# RFBoardLayoutGen0_v03_1routingTADworking.net
KiCad netlist of a schematic drawn in EAGLE
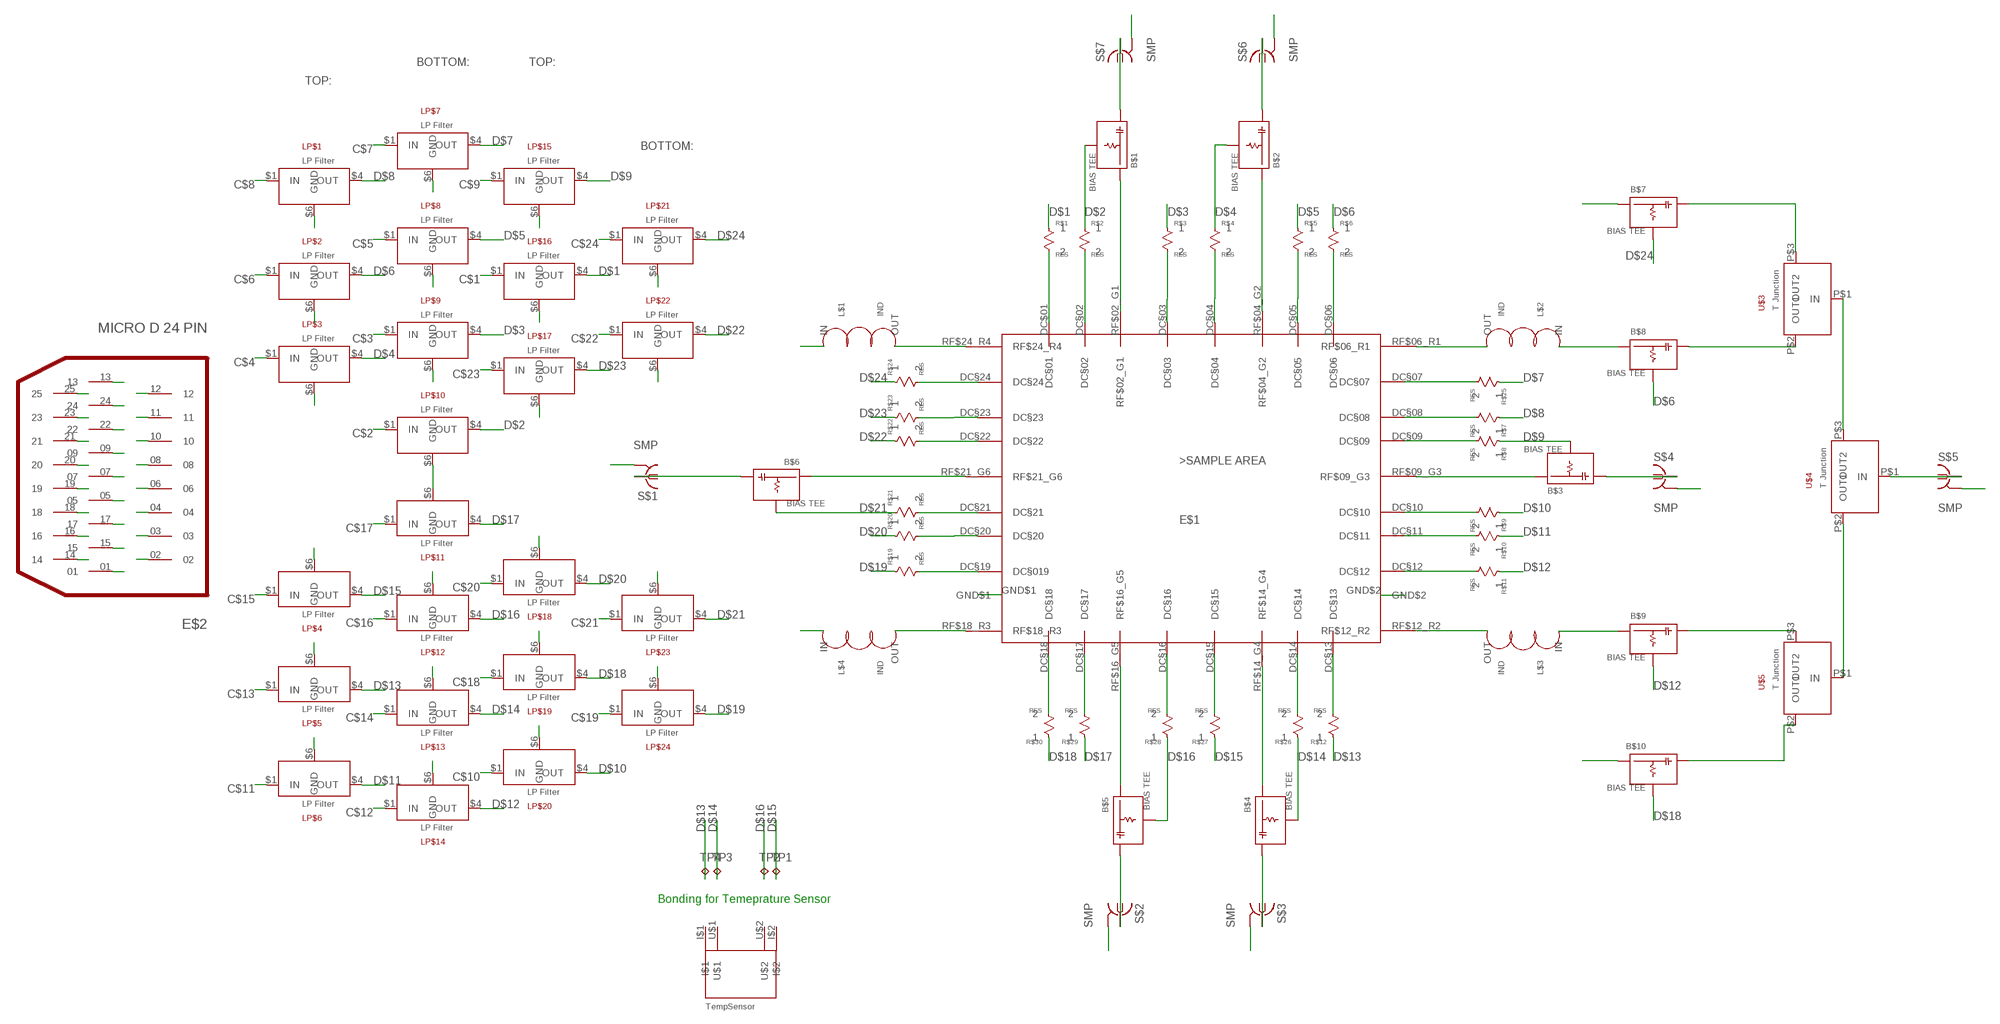
[diagram p0: schematic, sheet 1, part 1 of 2]
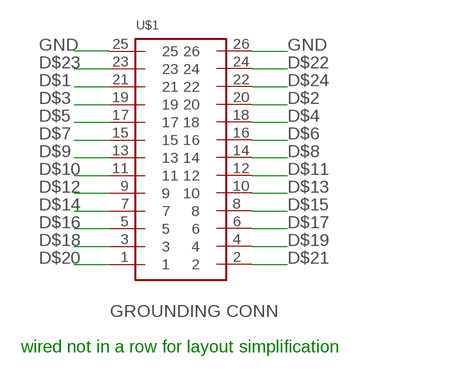
[diagram p1: schematic, sheet 1, part 2 of 2]

(export (version "E")
  (design (tool "Eeschema 10.0.6"))
  (components
    (comp (ref "B$1")
      (value "BIASTEEDOWN")
      (footprint "eagle-import:BIAS_TEE_DOWN_0603")
      (libsource (lib "eagle-import") (part "BIASTEEDOWN"))
    )
    (comp (ref "B$2")
      (value "BIASTEEUP")
      (footprint "eagle-import:BIAS_TEE_UP_0603")
      (libsource (lib "eagle-import") (part "BIASTEEUP"))
    )
    (comp (ref "B$3")
      (value "BIASTEEDOWN")
      (footprint "eagle-import:BIAS_TEE_DOWN_0603")
      (libsource (lib "eagle-import") (part "BIASTEEDOWN"))
    )
    (comp (ref "B$4")
      (value "BIASTEEDOWN")
      (footprint "eagle-import:BIAS_TEE_DOWN_0603")
      (libsource (lib "eagle-import") (part "BIASTEEDOWN"))
    )
    (comp (ref "B$5")
      (value "BIASTEEUP")
      (footprint "eagle-import:BIAS_TEE_UP_0603")
      (libsource (lib "eagle-import") (part "BIASTEEUP"))
    )
    (comp (ref "B$6")
      (value "BIASTEEDOWN")
      (footprint "eagle-import:BIAS_TEE_DOWN_0603")
      (libsource (lib "eagle-import") (part "BIASTEEDOWN"))
    )
    (comp (ref "B$7")
      (value "BIASTEEUP")
      (footprint "eagle-import:BIAS_TEE_UP_0603")
      (libsource (lib "eagle-import") (part "BIASTEEUP"))
    )
    (comp (ref "B$8")
      (value "BIASTEEDOWN")
      (footprint "eagle-import:BIAS_TEE_DOWN_0603")
      (libsource (lib "eagle-import") (part "BIASTEEDOWN"))
    )
    (comp (ref "B$9")
      (value "BIASTEEUP")
      (footprint "eagle-import:BIAS_TEE_UP_0603")
      (libsource (lib "eagle-import") (part "BIASTEEUP"))
    )
    (comp (ref "B$10")
      (value "BIASTEEDOWN")
      (footprint "eagle-import:BIAS_TEE_DOWN_0603")
      (libsource (lib "eagle-import") (part "BIASTEEDOWN"))
    )
    (comp (ref "E$1")
      (value "24DC+10RF")
      (footprint "eagle-import:24DC+10RF_400MU-PADS_0.7X0.7_V1.0")
      (libsource (lib "eagle-import") (part "24DC+10RF"))
    )
    (comp (ref "E$2")
      (value "25_SOCKET_M83513(13-DPINOUT2")
      (footprint "eagle-import:25_SOCKET_M83513_13-D_V2")
      (libsource (lib "eagle-import") (part "25_SOCKET_M83513(13-DPINOUT2"))
    )
    (comp (ref "L$1")
      (value "L_MATCH")
      (footprint "eagle-import:L_MATCH")
      (libsource (lib "eagle-import") (part "L_MATCH"))
    )
    (comp (ref "L$2")
      (value "L_MATCH")
      (footprint "eagle-import:L_MATCH")
      (libsource (lib "eagle-import") (part "L_MATCH"))
    )
    (comp (ref "L$3")
      (value "L_MATCH")
      (footprint "eagle-import:L_MATCH")
      (libsource (lib "eagle-import") (part "L_MATCH"))
    )
    (comp (ref "L$4")
      (value "L_MATCH")
      (footprint "eagle-import:L_MATCH")
      (libsource (lib "eagle-import") (part "L_MATCH"))
    )
    (comp (ref "LP$1")
      (value "LP-FILTER/1-STAGETOP")
      (footprint "eagle-import:LP-FILTER_1_STAGE_OS_0603_TOP")
      (libsource (lib "eagle-import") (part "LP-FILTER/1-STAGETOP"))
    )
    (comp (ref "LP$2")
      (value "LP-FILTER/1-STAGETOP")
      (footprint "eagle-import:LP-FILTER_1_STAGE_OS_0603_TOP")
      (libsource (lib "eagle-import") (part "LP-FILTER/1-STAGETOP"))
    )
    (comp (ref "LP$3")
      (value "LP-FILTER/1-STAGETOP")
      (footprint "eagle-import:LP-FILTER_1_STAGE_OS_0603_TOP")
      (libsource (lib "eagle-import") (part "LP-FILTER/1-STAGETOP"))
    )
    (comp (ref "LP$4")
      (value "LP-FILTER/1-STAGETOP")
      (footprint "eagle-import:LP-FILTER_1_STAGE_OS_0603_TOP")
      (libsource (lib "eagle-import") (part "LP-FILTER/1-STAGETOP"))
    )
    (comp (ref "LP$5")
      (value "LP-FILTER/1-STAGETOP")
      (footprint "eagle-import:LP-FILTER_1_STAGE_OS_0603_TOP")
      (libsource (lib "eagle-import") (part "LP-FILTER/1-STAGETOP"))
    )
    (comp (ref "LP$6")
      (value "LP-FILTER/1-STAGETOP")
      (footprint "eagle-import:LP-FILTER_1_STAGE_OS_0603_TOP")
      (libsource (lib "eagle-import") (part "LP-FILTER/1-STAGETOP"))
    )
    (comp (ref "LP$7")
      (value "LP-FILTER/1-STAGEBOT")
      (footprint "eagle-import:LP-FILTER_1_STAGE_OS_0603_BOTTOM")
      (libsource (lib "eagle-import") (part "LP-FILTER/1-STAGEBOT"))
    )
    (comp (ref "LP$8")
      (value "LP-FILTER/1-STAGEBOT")
      (footprint "eagle-import:LP-FILTER_1_STAGE_OS_0603_BOTTOM")
      (libsource (lib "eagle-import") (part "LP-FILTER/1-STAGEBOT"))
    )
    (comp (ref "LP$9")
      (value "LP-FILTER/1-STAGEBOT")
      (footprint "eagle-import:LP-FILTER_1_STAGE_OS_0603_BOTTOM")
      (libsource (lib "eagle-import") (part "LP-FILTER/1-STAGEBOT"))
    )
    (comp (ref "LP$10")
      (value "LP-FILTER/1-STAGEBOT")
      (footprint "eagle-import:LP-FILTER_1_STAGE_OS_0603_BOTTOM")
      (libsource (lib "eagle-import") (part "LP-FILTER/1-STAGEBOT"))
    )
    (comp (ref "LP$11")
      (value "LP-FILTER/1-STAGEBOT")
      (footprint "eagle-import:LP-FILTER_1_STAGE_OS_0603_BOTTOM")
      (libsource (lib "eagle-import") (part "LP-FILTER/1-STAGEBOT"))
    )
    (comp (ref "LP$12")
      (value "LP-FILTER/1-STAGEBOT")
      (footprint "eagle-import:LP-FILTER_1_STAGE_OS_0603_BOTTOM")
      (libsource (lib "eagle-import") (part "LP-FILTER/1-STAGEBOT"))
    )
    (comp (ref "LP$13")
      (value "LP-FILTER/1-STAGEBOT")
      (footprint "eagle-import:LP-FILTER_1_STAGE_OS_0603_BOTTOM")
      (libsource (lib "eagle-import") (part "LP-FILTER/1-STAGEBOT"))
    )
    (comp (ref "LP$14")
      (value "LP-FILTER/1-STAGEBOT")
      (footprint "eagle-import:LP-FILTER_1_STAGE_OS_0603_BOTTOM")
      (libsource (lib "eagle-import") (part "LP-FILTER/1-STAGEBOT"))
    )
    (comp (ref "LP$15")
      (value "LP-FILTER/1-STAGETOP")
      (footprint "eagle-import:LP-FILTER_1_STAGE_OS_0603_TOP")
      (libsource (lib "eagle-import") (part "LP-FILTER/1-STAGETOP"))
    )
    (comp (ref "LP$16")
      (value "LP-FILTER/1-STAGETOP")
      (footprint "eagle-import:LP-FILTER_1_STAGE_OS_0603_TOP")
      (libsource (lib "eagle-import") (part "LP-FILTER/1-STAGETOP"))
    )
    (comp (ref "LP$17")
      (value "LP-FILTER/1-STAGETOP")
      (footprint "eagle-import:LP-FILTER_1_STAGE_OS_0603_TOP")
      (libsource (lib "eagle-import") (part "LP-FILTER/1-STAGETOP"))
    )
    (comp (ref "LP$18")
      (value "LP-FILTER/1-STAGETOP")
      (footprint "eagle-import:LP-FILTER_1_STAGE_OS_0603_TOP")
      (libsource (lib "eagle-import") (part "LP-FILTER/1-STAGETOP"))
    )
    (comp (ref "LP$19")
      (value "LP-FILTER/1-STAGETOP")
      (footprint "eagle-import:LP-FILTER_1_STAGE_OS_0603_TOP")
      (libsource (lib "eagle-import") (part "LP-FILTER/1-STAGETOP"))
    )
    (comp (ref "LP$20")
      (value "LP-FILTER/1-STAGETOP")
      (footprint "eagle-import:LP-FILTER_1_STAGE_OS_0603_TOP")
      (libsource (lib "eagle-import") (part "LP-FILTER/1-STAGETOP"))
    )
    (comp (ref "LP$21")
      (value "LP-FILTER/1-STAGEBOT")
      (footprint "eagle-import:LP-FILTER_1_STAGE_OS_0603_BOTTOM")
      (libsource (lib "eagle-import") (part "LP-FILTER/1-STAGEBOT"))
    )
    (comp (ref "LP$22")
      (value "LP-FILTER/1-STAGEBOT")
      (footprint "eagle-import:LP-FILTER_1_STAGE_OS_0603_BOTTOM")
      (libsource (lib "eagle-import") (part "LP-FILTER/1-STAGEBOT"))
    )
    (comp (ref "LP$23")
      (value "LP-FILTER/1-STAGEBOT")
      (footprint "eagle-import:LP-FILTER_1_STAGE_OS_0603_BOTTOM")
      (libsource (lib "eagle-import") (part "LP-FILTER/1-STAGEBOT"))
    )
    (comp (ref "LP$24")
      (value "LP-FILTER/1-STAGEBOT")
      (footprint "eagle-import:LP-FILTER_1_STAGE_OS_0603_BOTTOM")
      (libsource (lib "eagle-import") (part "LP-FILTER/1-STAGEBOT"))
    )
    (comp (ref "R$1")
      (value "10K")
      (footprint "eagle-import:LP-FILTER_RESISTOR_0603_BOTTOM")
      (libsource (lib "eagle-import") (part "LP-FILTER/RESISTOR/0603"))
    )
    (comp (ref "R$2")
      (value "10K")
      (footprint "eagle-import:LP-FILTER_RESISTOR_0603_BOTTOM")
      (libsource (lib "eagle-import") (part "LP-FILTER/RESISTOR/0603"))
    )
    (comp (ref "R$3")
      (value "10K")
      (footprint "eagle-import:LP-FILTER_RESISTOR_0603_BOTTOM")
      (libsource (lib "eagle-import") (part "LP-FILTER/RESISTOR/0603"))
    )
    (comp (ref "R$4")
      (value "10K")
      (footprint "eagle-import:LP-FILTER_RESISTOR_0603_BOTTOM")
      (libsource (lib "eagle-import") (part "LP-FILTER/RESISTOR/0603"))
    )
    (comp (ref "R$5")
      (value "10K")
      (footprint "eagle-import:LP-FILTER_RESISTOR_0603_BOTTOM")
      (libsource (lib "eagle-import") (part "LP-FILTER/RESISTOR/0603"))
    )
    (comp (ref "R$6")
      (value "10K")
      (footprint "eagle-import:LP-FILTER_RESISTOR_0603_BOTTOM")
      (libsource (lib "eagle-import") (part "LP-FILTER/RESISTOR/0603"))
    )
    (comp (ref "R$7")
      (value "10K")
      (footprint "eagle-import:LP-FILTER_RESISTOR_0603_BOTTOM")
      (libsource (lib "eagle-import") (part "LP-FILTER/RESISTOR/0603"))
    )
    (comp (ref "R$8")
      (value "10K")
      (footprint "eagle-import:LP-FILTER_RESISTOR_0603_BOTTOM")
      (libsource (lib "eagle-import") (part "LP-FILTER/RESISTOR/0603"))
    )
    (comp (ref "R$9")
      (value "10K")
      (footprint "eagle-import:LP-FILTER_RESISTOR_0603_BOTTOM")
      (libsource (lib "eagle-import") (part "LP-FILTER/RESISTOR/0603"))
    )
    (comp (ref "R$10")
      (value "10K")
      (footprint "eagle-import:LP-FILTER_RESISTOR_0603_BOTTOM")
      (libsource (lib "eagle-import") (part "LP-FILTER/RESISTOR/0603"))
    )
    (comp (ref "R$11")
      (value "10K")
      (footprint "eagle-import:LP-FILTER_RESISTOR_0603_BOTTOM")
      (libsource (lib "eagle-import") (part "LP-FILTER/RESISTOR/0603"))
    )
    (comp (ref "R$12")
      (value "10K")
      (footprint "eagle-import:LP-FILTER_RESISTOR_0603_BOTTOM")
      (libsource (lib "eagle-import") (part "LP-FILTER/RESISTOR/0603"))
    )
    (comp (ref "R$19")
      (value "10K")
      (footprint "eagle-import:LP-FILTER_RESISTOR_0603_BOTTOM")
      (libsource (lib "eagle-import") (part "LP-FILTER/RESISTOR/0603"))
    )
    (comp (ref "R$20")
      (value "10K")
      (footprint "eagle-import:LP-FILTER_RESISTOR_0603_BOTTOM")
      (libsource (lib "eagle-import") (part "LP-FILTER/RESISTOR/0603"))
    )
    (comp (ref "R$21")
      (value "10K")
      (footprint "eagle-import:LP-FILTER_RESISTOR_0603_BOTTOM")
      (libsource (lib "eagle-import") (part "LP-FILTER/RESISTOR/0603"))
    )
    (comp (ref "R$22")
      (value "10K")
      (footprint "eagle-import:LP-FILTER_RESISTOR_0603_BOTTOM")
      (libsource (lib "eagle-import") (part "LP-FILTER/RESISTOR/0603"))
    )
    (comp (ref "R$23")
      (value "10K")
      (footprint "eagle-import:LP-FILTER_RESISTOR_0603_BOTTOM")
      (libsource (lib "eagle-import") (part "LP-FILTER/RESISTOR/0603"))
    )
    (comp (ref "R$24")
      (value "10K")
      (footprint "eagle-import:LP-FILTER_RESISTOR_0603_BOTTOM")
      (libsource (lib "eagle-import") (part "LP-FILTER/RESISTOR/0603"))
    )
    (comp (ref "R$25")
      (value "10K")
      (footprint "eagle-import:LP-FILTER_RESISTOR_0603_BOTTOM")
      (libsource (lib "eagle-import") (part "LP-FILTER/RESISTOR/0603"))
    )
    (comp (ref "R$26")
      (value "10K")
      (footprint "eagle-import:LP-FILTER_RESISTOR_0603_BOTTOM")
      (libsource (lib "eagle-import") (part "LP-FILTER/RESISTOR/0603"))
    )
    (comp (ref "R$27")
      (value "10K")
      (footprint "eagle-import:LP-FILTER_RESISTOR_0603_BOTTOM")
      (libsource (lib "eagle-import") (part "LP-FILTER/RESISTOR/0603"))
    )
    (comp (ref "R$28")
      (value "10K")
      (footprint "eagle-import:LP-FILTER_RESISTOR_0603_BOTTOM")
      (libsource (lib "eagle-import") (part "LP-FILTER/RESISTOR/0603"))
    )
    (comp (ref "R$29")
      (value "10K")
      (footprint "eagle-import:LP-FILTER_RESISTOR_0603_BOTTOM")
      (libsource (lib "eagle-import") (part "LP-FILTER/RESISTOR/0603"))
    )
    (comp (ref "R$30")
      (value "10K")
      (footprint "eagle-import:LP-FILTER_RESISTOR_0603_BOTTOM")
      (libsource (lib "eagle-import") (part "LP-FILTER/RESISTOR/0603"))
    )
    (comp (ref "S$1")
      (value "MC-921")
      (footprint "eagle-import:SMP_STRAIGHT_MINI")
      (libsource (lib "eagle-import") (part "MC-921"))
    )
    (comp (ref "S$2")
      (value "MC-921")
      (footprint "eagle-import:SMP_STRAIGHT_MINI")
      (libsource (lib "eagle-import") (part "MC-921"))
    )
    (comp (ref "S$3")
      (value "MC-921")
      (footprint "eagle-import:SMP_STRAIGHT_MINI")
      (libsource (lib "eagle-import") (part "MC-921"))
    )
    (comp (ref "S$4")
      (value "MC-921")
      (footprint "eagle-import:SMP_STRAIGHT_MINI")
      (libsource (lib "eagle-import") (part "MC-921"))
    )
    (comp (ref "S$5")
      (value "MC-921")
      (footprint "eagle-import:SMP_STRAIGHT_MINI")
      (libsource (lib "eagle-import") (part "MC-921"))
    )
    (comp (ref "S$6")
      (value "MC-921")
      (footprint "eagle-import:SMP_STRAIGHT_MINI")
      (libsource (lib "eagle-import") (part "MC-921"))
    )
    (comp (ref "S$7")
      (value "MC-921")
      (footprint "eagle-import:SMP_STRAIGHT_MINI")
      (libsource (lib "eagle-import") (part "MC-921"))
    )
    (comp (ref "TP1")
      (value "TPTP07SQ")
      (footprint "eagle-import:TP07SQ")
      (libsource (lib "eagle-import") (part "TPTP07SQ"))
    )
    (comp (ref "TP2")
      (value "TPTP07SQ")
      (footprint "eagle-import:TP07SQ")
      (libsource (lib "eagle-import") (part "TPTP07SQ"))
    )
    (comp (ref "TP3")
      (value "TPTP07SQ")
      (footprint "eagle-import:TP07SQ")
      (libsource (lib "eagle-import") (part "TPTP07SQ"))
    )
    (comp (ref "TP4")
      (value "TPTP07SQ")
      (footprint "eagle-import:TP07SQ")
      (libsource (lib "eagle-import") (part "TPTP07SQ"))
    )
    (comp (ref "U$1")
      (value "MEC8-113-02-L-D-RA1MBRD")
      (footprint "eagle-import:MEC8-113-02-L-D-RA1")
      (libsource (lib "eagle-import") (part "MEC8-113-02-L-D-RA1MBRD"))
    )
    (comp (ref "U$2")
      (value "TEMPSENS")
      (footprint "eagle-import:RX-BR_V1")
      (libsource (lib "eagle-import") (part "TEMPSENS"))
    )
    (comp (ref "U$3")
      (value "TJUNCTION")
      (footprint "eagle-import:T_JUNCTION_0.3MM")
      (libsource (lib "eagle-import") (part "TJUNCTION"))
    )
    (comp (ref "U$4")
      (value "TJUNCTION")
      (footprint "eagle-import:T_JUNCTION_0.3MM")
      (libsource (lib "eagle-import") (part "TJUNCTION"))
    )
    (comp (ref "U$5")
      (value "TJUNCTION")
      (footprint "eagle-import:T_JUNCTION_0.3MM")
      (libsource (lib "eagle-import") (part "TJUNCTION"))
    )
  )
  (nets
    (net (code "1") (name "/C$1") (class "Default")
      (node (ref "E$2") (pin "01") (pinfunction "01_01") (pintype "bidirectional"))
      (node (ref "LP$16") (pin "$1") (pinfunction "IN_$1") (pintype "bidirectional"))
    )
    (net (code "2") (name "/C$2") (class "Default")
      (node (ref "E$2") (pin "02") (pinfunction "02_02") (pintype "bidirectional"))
      (node (ref "LP$10") (pin "$1") (pinfunction "IN_$1") (pintype "bidirectional"))
    )
    (net (code "3") (name "/C$3") (class "Default")
      (node (ref "E$2") (pin "03") (pinfunction "03_03") (pintype "bidirectional"))
      (node (ref "LP$9") (pin "$1") (pinfunction "IN_$1") (pintype "bidirectional"))
    )
    (net (code "4") (name "/C$4") (class "Default")
      (node (ref "E$2") (pin "04") (pinfunction "04_04") (pintype "bidirectional"))
      (node (ref "LP$3") (pin "$1") (pinfunction "IN_$1") (pintype "bidirectional"))
    )
    (net (code "5") (name "/C$5") (class "Default")
      (node (ref "E$2") (pin "05") (pinfunction "05_05") (pintype "bidirectional"))
      (node (ref "LP$8") (pin "$1") (pinfunction "IN_$1") (pintype "bidirectional"))
    )
    (net (code "6") (name "/C$6") (class "Default")
      (node (ref "E$2") (pin "06") (pinfunction "06_06") (pintype "bidirectional"))
      (node (ref "LP$2") (pin "$1") (pinfunction "IN_$1") (pintype "bidirectional"))
    )
    (net (code "7") (name "/C$7") (class "Default")
      (node (ref "E$2") (pin "07") (pinfunction "07_07") (pintype "bidirectional"))
      (node (ref "LP$7") (pin "$1") (pinfunction "IN_$1") (pintype "bidirectional"))
    )
    (net (code "8") (name "/C$8") (class "Default")
      (node (ref "E$2") (pin "08") (pinfunction "08_08") (pintype "bidirectional"))
      (node (ref "LP$1") (pin "$1") (pinfunction "IN_$1") (pintype "bidirectional"))
    )
    (net (code "9") (name "/C$9") (class "Default")
      (node (ref "E$2") (pin "09") (pinfunction "09_09") (pintype "bidirectional"))
      (node (ref "LP$15") (pin "$1") (pinfunction "IN_$1") (pintype "bidirectional"))
    )
    (net (code "10") (name "/C$10") (class "Default")
      (node (ref "E$2") (pin "10") (pinfunction "10_10") (pintype "bidirectional"))
      (node (ref "LP$20") (pin "$1") (pinfunction "IN_$1") (pintype "bidirectional"))
    )
    (net (code "11") (name "/C$11") (class "Default")
      (node (ref "E$2") (pin "11") (pinfunction "11_11") (pintype "bidirectional"))
      (node (ref "LP$6") (pin "$1") (pinfunction "IN_$1") (pintype "bidirectional"))
    )
    (net (code "12") (name "/C$12") (class "Default")
      (node (ref "E$2") (pin "12") (pinfunction "12_12") (pintype "bidirectional"))
      (node (ref "LP$14") (pin "$1") (pinfunction "IN_$1") (pintype "bidirectional"))
    )
    (net (code "13") (name "/C$13") (class "Default")
      (node (ref "E$2") (pin "13") (pinfunction "13_13") (pintype "bidirectional"))
      (node (ref "LP$5") (pin "$1") (pinfunction "IN_$1") (pintype "bidirectional"))
    )
    (net (code "14") (name "/C$14") (class "Default")
      (node (ref "E$2") (pin "14") (pinfunction "14_14") (pintype "bidirectional"))
      (node (ref "LP$13") (pin "$1") (pinfunction "IN_$1") (pintype "bidirectional"))
    )
    (net (code "15") (name "/C$15") (class "Default")
      (node (ref "E$2") (pin "15") (pinfunction "15_15") (pintype "bidirectional"))
      (node (ref "LP$4") (pin "$1") (pinfunction "IN_$1") (pintype "bidirectional"))
    )
    (net (code "16") (name "/C$16") (class "Default")
      (node (ref "E$2") (pin "16") (pinfunction "16_16") (pintype "bidirectional"))
      (node (ref "LP$12") (pin "$1") (pinfunction "IN_$1") (pintype "bidirectional"))
    )
    (net (code "17") (name "/C$17") (class "Default")
      (node (ref "E$2") (pin "17") (pinfunction "17_17") (pintype "bidirectional"))
      (node (ref "LP$11") (pin "$1") (pinfunction "IN_$1") (pintype "bidirectional"))
    )
    (net (code "18") (name "/C$18") (class "Default")
      (node (ref "E$2") (pin "18") (pinfunction "18_18") (pintype "bidirectional"))
      (node (ref "LP$19") (pin "$1") (pinfunction "IN_$1") (pintype "bidirectional"))
    )
    (net (code "19") (name "/C$19") (class "Default")
      (node (ref "E$2") (pin "19") (pinfunction "19_19") (pintype "bidirectional"))
      (node (ref "LP$24") (pin "$1") (pinfunction "IN_$1") (pintype "bidirectional"))
    )
    (net (code "20") (name "/C$20") (class "Default")
      (node (ref "E$2") (pin "20") (pinfunction "20_20") (pintype "bidirectional"))
      (node (ref "LP$18") (pin "$1") (pinfunction "IN_$1") (pintype "bidirectional"))
    )
    (net (code "21") (name "/C$21") (class "Default")
      (node (ref "E$2") (pin "21") (pinfunction "21_21") (pintype "bidirectional"))
      (node (ref "LP$23") (pin "$1") (pinfunction "IN_$1") (pintype "bidirectional"))
    )
    (net (code "22") (name "/C$22") (class "Default")
      (node (ref "E$2") (pin "22") (pinfunction "22_22") (pintype "bidirectional"))
      (node (ref "LP$22") (pin "$1") (pinfunction "IN_$1") (pintype "bidirectional"))
    )
    (net (code "23") (name "/C$23") (class "Default")
      (node (ref "E$2") (pin "23") (pinfunction "23_23") (pintype "bidirectional"))
      (node (ref "LP$17") (pin "$1") (pinfunction "IN_$1") (pintype "bidirectional"))
    )
    (net (code "24") (name "/C$24") (class "Default")
      (node (ref "E$2") (pin "24") (pinfunction "24_24") (pintype "bidirectional"))
      (node (ref "LP$21") (pin "$1") (pinfunction "IN_$1") (pintype "bidirectional"))
    )
    (net (code "25") (name "/D$1") (class "Default")
      (node (ref "LP$16") (pin "$4") (pinfunction "OUT_$4") (pintype "bidirectional"))
      (node (ref "R$1") (pin "IN") (pinfunction "1_IN") (pintype "passive"))
      (node (ref "U$1") (pin "21") (pinfunction "21_21") (pintype "bidirectional"))
    )
    (net (code "26") (name "/D$2") (class "Default")
      (node (ref "B$1") (pin "LF") (pinfunction "LF_LF") (pintype "bidirectional"))
      (node (ref "LP$10") (pin "$4") (pinfunction "OUT_$4") (pintype "bidirectional"))
      (node (ref "R$2") (pin "IN") (pinfunction "1_IN") (pintype "passive"))
      (node (ref "U$1") (pin "20") (pinfunction "20_20") (pintype "bidirectional"))
    )
    (net (code "27") (name "/D$3") (class "Default")
      (node (ref "LP$9") (pin "$4") (pinfunction "OUT_$4") (pintype "bidirectional"))
      (node (ref "R$3") (pin "IN") (pinfunction "1_IN") (pintype "passive"))
      (node (ref "U$1") (pin "19") (pinfunction "19_19") (pintype "bidirectional"))
    )
    (net (code "28") (name "/D$4") (class "Default")
      (node (ref "B$2") (pin "LF") (pinfunction "LF_LF") (pintype "bidirectional"))
      (node (ref "LP$3") (pin "$4") (pinfunction "OUT_$4") (pintype "bidirectional"))
      (node (ref "R$4") (pin "IN") (pinfunction "1_IN") (pintype "passive"))
      (node (ref "U$1") (pin "18") (pinfunction "18_18") (pintype "bidirectional"))
    )
    (net (code "29") (name "/D$5") (class "Default")
      (node (ref "LP$8") (pin "$4") (pinfunction "OUT_$4") (pintype "bidirectional"))
      (node (ref "R$5") (pin "IN") (pinfunction "1_IN") (pintype "passive"))
      (node (ref "U$1") (pin "17") (pinfunction "17_17") (pintype "bidirectional"))
    )
    (net (code "30") (name "/D$6") (class "Default")
      (node (ref "B$8") (pin "LF") (pinfunction "LF_LF") (pintype "bidirectional"))
      (node (ref "LP$2") (pin "$4") (pinfunction "OUT_$4") (pintype "bidirectional"))
      (node (ref "R$6") (pin "IN") (pinfunction "1_IN") (pintype "passive"))
      (node (ref "U$1") (pin "16") (pinfunction "16_16") (pintype "bidirectional"))
    )
    (net (code "31") (name "/D$7") (class "Default")
      (node (ref "LP$7") (pin "$4") (pinfunction "OUT_$4") (pintype "bidirectional"))
      (node (ref "R$25") (pin "IN") (pinfunction "1_IN") (pintype "passive"))
      (node (ref "U$1") (pin "15") (pinfunction "15_15") (pintype "bidirectional"))
    )
    (net (code "32") (name "/D$8") (class "Default")
      (node (ref "LP$1") (pin "$4") (pinfunction "OUT_$4") (pintype "bidirectional"))
      (node (ref "R$7") (pin "IN") (pinfunction "1_IN") (pintype "passive"))
      (node (ref "U$1") (pin "14") (pinfunction "14_14") (pintype "bidirectional"))
    )
    (net (code "33") (name "/D$9") (class "Default")
      (node (ref "B$3") (pin "LF") (pinfunction "LF_LF") (pintype "bidirectional"))
      (node (ref "LP$15") (pin "$4") (pinfunction "OUT_$4") (pintype "bidirectional"))
      (node (ref "R$8") (pin "IN") (pinfunction "1_IN") (pintype "passive"))
      (node (ref "U$1") (pin "13") (pinfunction "13_13") (pintype "bidirectional"))
    )
    (net (code "34") (name "/D$10") (class "Default")
      (node (ref "LP$20") (pin "$4") (pinfunction "OUT_$4") (pintype "bidirectional"))
      (node (ref "R$9") (pin "IN") (pinfunction "1_IN") (pintype "passive"))
      (node (ref "U$1") (pin "11") (pinfunction "11_11") (pintype "bidirectional"))
    )
    (net (code "35") (name "/D$11") (class "Default")
      (node (ref "LP$6") (pin "$4") (pinfunction "OUT_$4") (pintype "bidirectional"))
      (node (ref "R$10") (pin "IN") (pinfunction "1_IN") (pintype "passive"))
      (node (ref "U$1") (pin "12") (pinfunction "12_12") (pintype "bidirectional"))
    )
    (net (code "36") (name "/D$12") (class "Default")
      (node (ref "B$9") (pin "LF") (pinfunction "LF_LF") (pintype "bidirectional"))
      (node (ref "LP$14") (pin "$4") (pinfunction "OUT_$4") (pintype "bidirectional"))
      (node (ref "R$11") (pin "IN") (pinfunction "1_IN") (pintype "passive"))
      (node (ref "U$1") (pin "9") (pinfunction "9_9") (pintype "bidirectional"))
    )
    (net (code "37") (name "/D$13") (class "Default")
      (node (ref "LP$5") (pin "$4") (pinfunction "OUT_$4") (pintype "bidirectional"))
      (node (ref "R$12") (pin "IN") (pinfunction "1_IN") (pintype "passive"))
      (node (ref "TP4") (pin "TP") (pinfunction "TP_TP") (pintype "input"))
      (node (ref "U$1") (pin "10") (pinfunction "10_10") (pintype "bidirectional"))
    )
    (net (code "38") (name "/D$14") (class "Default")
      (node (ref "B$4") (pin "LF") (pinfunction "LF_LF") (pintype "bidirectional"))
      (node (ref "LP$13") (pin "$4") (pinfunction "OUT_$4") (pintype "bidirectional"))
      (node (ref "R$26") (pin "IN") (pinfunction "1_IN") (pintype "passive"))
      (node (ref "TP3") (pin "TP") (pinfunction "TP_TP") (pintype "input"))
      (node (ref "U$1") (pin "7") (pinfunction "7_7") (pintype "bidirectional"))
    )
    (net (code "39") (name "/D$15") (class "Default")
      (node (ref "LP$4") (pin "$4") (pinfunction "OUT_$4") (pintype "bidirectional"))
      (node (ref "R$27") (pin "IN") (pinfunction "1_IN") (pintype "passive"))
      (node (ref "TP1") (pin "TP") (pinfunction "TP_TP") (pintype "input"))
      (node (ref "U$1") (pin "8") (pinfunction "8_8") (pintype "bidirectional"))
    )
    (net (code "40") (name "/D$16") (class "Default")
      (node (ref "B$5") (pin "LF") (pinfunction "LF_LF") (pintype "bidirectional"))
      (node (ref "LP$12") (pin "$4") (pinfunction "OUT_$4") (pintype "bidirectional"))
      (node (ref "R$28") (pin "IN") (pinfunction "1_IN") (pintype "passive"))
      (node (ref "TP2") (pin "TP") (pinfunction "TP_TP") (pintype "input"))
      (node (ref "U$1") (pin "5") (pinfunction "5_5") (pintype "bidirectional"))
    )
    (net (code "41") (name "/D$17") (class "Default")
      (node (ref "LP$11") (pin "$4") (pinfunction "OUT_$4") (pintype "bidirectional"))
      (node (ref "R$29") (pin "IN") (pinfunction "1_IN") (pintype "passive"))
      (node (ref "U$1") (pin "6") (pinfunction "6_6") (pintype "bidirectional"))
    )
    (net (code "42") (name "/D$18") (class "Default")
      (node (ref "B$10") (pin "LF") (pinfunction "LF_LF") (pintype "bidirectional"))
      (node (ref "LP$19") (pin "$4") (pinfunction "OUT_$4") (pintype "bidirectional"))
      (node (ref "R$30") (pin "IN") (pinfunction "1_IN") (pintype "passive"))
      (node (ref "U$1") (pin "3") (pinfunction "3_3") (pintype "bidirectional"))
    )
    (net (code "43") (name "/D$19") (class "Default")
      (node (ref "LP$24") (pin "$4") (pinfunction "OUT_$4") (pintype "bidirectional"))
      (node (ref "R$19") (pin "IN") (pinfunction "1_IN") (pintype "passive"))
      (node (ref "U$1") (pin "4") (pinfunction "4_4") (pintype "bidirectional"))
    )
    (net (code "44") (name "/D$20") (class "Default")
      (node (ref "LP$18") (pin "$4") (pinfunction "OUT_$4") (pintype "bidirectional"))
      (node (ref "R$20") (pin "IN") (pinfunction "1_IN") (pintype "passive"))
      (node (ref "U$1") (pin "1") (pinfunction "1_1") (pintype "bidirectional"))
    )
    (net (code "45") (name "/D$21") (class "Default")
      (node (ref "B$6") (pin "LF") (pinfunction "LF_LF") (pintype "bidirectional"))
      (node (ref "LP$23") (pin "$4") (pinfunction "OUT_$4") (pintype "bidirectional"))
      (node (ref "R$21") (pin "IN") (pinfunction "1_IN") (pintype "passive"))
      (node (ref "U$1") (pin "2") (pinfunction "2_2") (pintype "bidirectional"))
    )
    (net (code "46") (name "/D$22") (class "Default")
      (node (ref "LP$22") (pin "$4") (pinfunction "OUT_$4") (pintype "bidirectional"))
      (node (ref "R$22") (pin "IN") (pinfunction "1_IN") (pintype "passive"))
      (node (ref "U$1") (pin "24") (pinfunction "24_24") (pintype "bidirectional"))
    )
    (net (code "47") (name "/D$23") (class "Default")
      (node (ref "LP$17") (pin "$4") (pinfunction "OUT_$4") (pintype "bidirectional"))
      (node (ref "R$23") (pin "IN") (pinfunction "1_IN") (pintype "passive"))
      (node (ref "U$1") (pin "23") (pinfunction "23_23") (pintype "bidirectional"))
    )
    (net (code "48") (name "/D$24") (class "Default")
      (node (ref "B$7") (pin "LF") (pinfunction "LF_LF") (pintype "bidirectional"))
      (node (ref "LP$21") (pin "$4") (pinfunction "OUT_$4") (pintype "bidirectional"))
      (node (ref "R$24") (pin "IN") (pinfunction "1_IN") (pintype "passive"))
      (node (ref "U$1") (pin "22") (pinfunction "22_22") (pintype "bidirectional"))
    )
    (net (code "49") (name "/GND") (class "Default")
      (node (ref "E$1") (pin "GND$1") (pinfunction "GND$1_GND$1") (pintype "bidirectional"))
      (node (ref "E$1") (pin "GND$2") (pinfunction "GND$2_GND$2") (pintype "bidirectional"))
      (node (ref "E$2") (pin "25") (pinfunction "25_25") (pintype "bidirectional"))
      (node (ref "LP$1") (pin "$6") (pinfunction "GND_$6") (pintype "bidirectional"))
      (node (ref "LP$10") (pin "$6") (pinfunction "GND_$6") (pintype "bidirectional"))
      (node (ref "LP$11") (pin "$6") (pinfunction "GND_$6") (pintype "bidirectional"))
      (node (ref "LP$12") (pin "$6") (pinfunction "GND_$6") (pintype "bidirectional"))
      (node (ref "LP$13") (pin "$6") (pinfunction "GND_$6") (pintype "bidirectional"))
      (node (ref "LP$14") (pin "$6") (pinfunction "GND_$6") (pintype "bidirectional"))
      (node (ref "LP$15") (pin "$6") (pinfunction "GND_$6") (pintype "bidirectional"))
      (node (ref "LP$16") (pin "$6") (pinfunction "GND_$6") (pintype "bidirectional"))
      (node (ref "LP$17") (pin "$6") (pinfunction "GND_$6") (pintype "bidirectional"))
      (node (ref "LP$18") (pin "$6") (pinfunction "GND_$6") (pintype "bidirectional"))
      (node (ref "LP$19") (pin "$6") (pinfunction "GND_$6") (pintype "bidirectional"))
      (node (ref "LP$2") (pin "$6") (pinfunction "GND_$6") (pintype "bidirectional"))
      (node (ref "LP$20") (pin "$6") (pinfunction "GND_$6") (pintype "bidirectional"))
      (node (ref "LP$21") (pin "$6") (pinfunction "GND_$6") (pintype "bidirectional"))
      (node (ref "LP$22") (pin "$6") (pinfunction "GND_$6") (pintype "bidirectional"))
      (node (ref "LP$23") (pin "$6") (pinfunction "GND_$6") (pintype "bidirectional"))
      (node (ref "LP$24") (pin "$6") (pinfunction "GND_$6") (pintype "bidirectional"))
      (node (ref "LP$3") (pin "$6") (pinfunction "GND_$6") (pintype "bidirectional"))
      (node (ref "LP$4") (pin "$6") (pinfunction "GND_$6") (pintype "bidirectional"))
      (node (ref "LP$5") (pin "$6") (pinfunction "GND_$6") (pintype "bidirectional"))
      (node (ref "LP$6") (pin "$6") (pinfunction "GND_$6") (pintype "bidirectional"))
      (node (ref "LP$7") (pin "$6") (pinfunction "GND_$6") (pintype "bidirectional"))
      (node (ref "LP$8") (pin "$6") (pinfunction "GND_$6") (pintype "bidirectional"))
      (node (ref "LP$9") (pin "$6") (pinfunction "GND_$6") (pintype "bidirectional"))
      (node (ref "S$1") (pin "2@1") (pinfunction "GND_2@1") (pintype "passive"))
      (node (ref "S$1") (pin "2@2") (pinfunction "GND_2@2") (pintype "passive"))
      (node (ref "S$2") (pin "2@1") (pinfunction "GND_2@1") (pintype "passive"))
      (node (ref "S$2") (pin "2@2") (pinfunction "GND_2@2") (pintype "passive"))
      (node (ref "S$3") (pin "2@1") (pinfunction "GND_2@1") (pintype "passive"))
      (node (ref "S$3") (pin "2@2") (pinfunction "GND_2@2") (pintype "passive"))
      (node (ref "S$4") (pin "2@1") (pinfunction "GND_2@1") (pintype "passive"))
      (node (ref "S$4") (pin "2@2") (pinfunction "GND_2@2") (pintype "passive"))
      (node (ref "S$5") (pin "2@1") (pinfunction "GND_2@1") (pintype "passive"))
      (node (ref "S$5") (pin "2@2") (pinfunction "GND_2@2") (pintype "passive"))
      (node (ref "S$6") (pin "2@1") (pinfunction "GND_2@1") (pintype "passive"))
      (node (ref "S$6") (pin "2@2") (pinfunction "GND_2@2") (pintype "passive"))
      (node (ref "S$7") (pin "2@1") (pinfunction "GND_2@1") (pintype "passive"))
      (node (ref "S$7") (pin "2@2") (pinfunction "GND_2@2") (pintype "passive"))
      (node (ref "U$1") (pin "25") (pinfunction "25_25") (pintype "bidirectional"))
      (node (ref "U$1") (pin "26") (pinfunction "26_26") (pintype "bidirectional"))
    )
    (net (code "50") (name "/RF$3") (class "Default")
      (node (ref "B$10") (pin "OUT") (pinfunction "OUT_OUT") (pintype "bidirectional"))
      (node (ref "L$4") (pin "IN") (pinfunction "IN_IN") (pintype "passive"))
    )
    (net (code "51") (name "/RF$4") (class "Default")
      (node (ref "B$7") (pin "OUT") (pinfunction "OUT_OUT") (pintype "bidirectional"))
      (node (ref "L$1") (pin "IN") (pinfunction "IN_IN") (pintype "passive"))
    )
    (net (code "52") (name "Net-(B$1-PadHF)") (class "Default")
      (node (ref "B$1") (pin "HF") (pinfunction "HF_HF") (pintype "bidirectional"))
      (node (ref "S$7") (pin "1") (pinfunction "1_1") (pintype "passive"))
    )
    (net (code "53") (name "Net-(B$1-PadOUT)") (class "Default")
      (node (ref "B$1") (pin "OUT") (pinfunction "OUT_OUT") (pintype "bidirectional"))
      (node (ref "E$1") (pin "RF$02_G1") (pinfunction "RF$02_G1_RF$02_G1") (pintype "bidirectional"))
    )
    (net (code "54") (name "Net-(B$2-PadHF)") (class "Default")
      (node (ref "B$2") (pin "HF") (pinfunction "HF_HF") (pintype "bidirectional"))
      (node (ref "S$6") (pin "1") (pinfunction "1_1") (pintype "passive"))
    )
    (net (code "55") (name "Net-(B$2-PadOUT)") (class "Default")
      (node (ref "B$2") (pin "OUT") (pinfunction "OUT_OUT") (pintype "bidirectional"))
      (node (ref "E$1") (pin "RF$04_G2") (pinfunction "RF$04_G2_RF$04_G2") (pintype "bidirectional"))
    )
    (net (code "56") (name "Net-(B$3-PadHF)") (class "Default")
      (node (ref "B$3") (pin "HF") (pinfunction "HF_HF") (pintype "bidirectional"))
      (node (ref "S$4") (pin "1") (pinfunction "1_1") (pintype "passive"))
    )
    (net (code "57") (name "Net-(B$3-PadOUT)") (class "Default")
      (node (ref "B$3") (pin "OUT") (pinfunction "OUT_OUT") (pintype "bidirectional"))
      (node (ref "E$1") (pin "RF$09_G3") (pinfunction "RF$09_G3_RF$09_G3") (pintype "bidirectional"))
    )
    (net (code "58") (name "Net-(B$4-PadHF)") (class "Default")
      (node (ref "B$4") (pin "HF") (pinfunction "HF_HF") (pintype "bidirectional"))
      (node (ref "S$3") (pin "1") (pinfunction "1_1") (pintype "passive"))
    )
    (net (code "59") (name "Net-(B$4-PadOUT)") (class "Default")
      (node (ref "B$4") (pin "OUT") (pinfunction "OUT_OUT") (pintype "bidirectional"))
      (node (ref "E$1") (pin "RF$14_G4") (pinfunction "RF$14_G4_RF$14_G4") (pintype "bidirectional"))
    )
    (net (code "60") (name "Net-(B$5-PadHF)") (class "Default")
      (node (ref "B$5") (pin "HF") (pinfunction "HF_HF") (pintype "bidirectional"))
      (node (ref "S$2") (pin "1") (pinfunction "1_1") (pintype "passive"))
    )
    (net (code "61") (name "Net-(B$5-PadOUT)") (class "Default")
      (node (ref "B$5") (pin "OUT") (pinfunction "OUT_OUT") (pintype "bidirectional"))
      (node (ref "E$1") (pin "RF$16_G5") (pinfunction "RF$16_G5_RF$16_G5") (pintype "bidirectional"))
    )
    (net (code "62") (name "Net-(B$6-PadHF)") (class "Default")
      (node (ref "B$6") (pin "HF") (pinfunction "HF_HF") (pintype "bidirectional"))
      (node (ref "S$1") (pin "1") (pinfunction "1_1") (pintype "passive"))
    )
    (net (code "63") (name "Net-(B$6-PadOUT)") (class "Default")
      (node (ref "B$6") (pin "OUT") (pinfunction "OUT_OUT") (pintype "bidirectional"))
      (node (ref "E$1") (pin "RF$21_G6") (pinfunction "RF$21_G6_RF$21_G6") (pintype "bidirectional"))
    )
    (net (code "64") (name "Net-(B$8-PadOUT)") (class "Default")
      (node (ref "B$8") (pin "OUT") (pinfunction "OUT_OUT") (pintype "bidirectional"))
      (node (ref "L$2") (pin "IN") (pinfunction "IN_IN") (pintype "passive"))
    )
    (net (code "65") (name "Net-(B$9-PadOUT)") (class "Default")
      (node (ref "B$9") (pin "OUT") (pinfunction "OUT_OUT") (pintype "bidirectional"))
      (node (ref "L$3") (pin "IN") (pinfunction "IN_IN") (pintype "passive"))
    )
    (net (code "66") (name "Net-(E$1-DC§01)") (class "Default")
      (node (ref "E$1") (pin "DC$01") (pinfunction "DC§01_DC$01") (pintype "bidirectional"))
      (node (ref "R$1") (pin "OUT") (pinfunction "2_OUT") (pintype "passive"))
    )
    (net (code "67") (name "Net-(E$1-DC§019)") (class "Default")
      (node (ref "E$1") (pin "DC§19") (pinfunction "DC§019_DC§19") (pintype "bidirectional"))
      (node (ref "R$19") (pin "OUT") (pinfunction "2_OUT") (pintype "passive"))
    )
    (net (code "68") (name "Net-(E$1-PadRF$06_R1)") (class "Default")
      (node (ref "E$1") (pin "RF$06_R1") (pinfunction "RF$06_R1_RF$06_R1") (pintype "bidirectional"))
      (node (ref "L$2") (pin "OUT") (pinfunction "OUT_OUT") (pintype "passive"))
    )
    (net (code "69") (name "Net-(E$1-PadRF$12_R2)") (class "Default")
      (node (ref "E$1") (pin "RF$12_R2") (pinfunction "RF$12_R2_RF$12_R2") (pintype "bidirectional"))
      (node (ref "L$3") (pin "OUT") (pinfunction "OUT_OUT") (pintype "passive"))
    )
    (net (code "70") (name "Net-(E$1-PadRF$18_R3)") (class "Default")
      (node (ref "E$1") (pin "RF$18_R3") (pinfunction "RF$18_R3_RF$18_R3") (pintype "bidirectional"))
      (node (ref "L$4") (pin "OUT") (pinfunction "OUT_OUT") (pintype "passive"))
    )
    (net (code "71") (name "Net-(E$1-PadRF$24_R4)") (class "Default")
      (node (ref "E$1") (pin "RF$24_R4") (pinfunction "RF$24_R4_RF$24_R4") (pintype "bidirectional"))
      (node (ref "L$1") (pin "OUT") (pinfunction "OUT_OUT") (pintype "passive"))
    )
    (net (code "72") (name "Net-(R$2-2)") (class "Default")
      (node (ref "E$1") (pin "DC§02") (pinfunction "DC§02_DC§02") (pintype "bidirectional"))
      (node (ref "R$2") (pin "OUT") (pinfunction "2_OUT") (pintype "passive"))
    )
    (net (code "73") (name "Net-(R$3-2)") (class "Default")
      (node (ref "E$1") (pin "DC§03") (pinfunction "DC§03_DC§03") (pintype "bidirectional"))
      (node (ref "R$3") (pin "OUT") (pinfunction "2_OUT") (pintype "passive"))
    )
    (net (code "74") (name "Net-(R$4-2)") (class "Default")
      (node (ref "E$1") (pin "DC§04") (pinfunction "DC§04_DC§04") (pintype "bidirectional"))
      (node (ref "R$4") (pin "OUT") (pinfunction "2_OUT") (pintype "passive"))
    )
    (net (code "75") (name "Net-(R$5-2)") (class "Default")
      (node (ref "E$1") (pin "DC§05") (pinfunction "DC§05_DC§05") (pintype "bidirectional"))
      (node (ref "R$5") (pin "OUT") (pinfunction "2_OUT") (pintype "passive"))
    )
    (net (code "76") (name "Net-(R$6-2)") (class "Default")
      (node (ref "E$1") (pin "DC§06") (pinfunction "DC§06_DC§06") (pintype "bidirectional"))
      (node (ref "R$6") (pin "OUT") (pinfunction "2_OUT") (pintype "passive"))
    )
    (net (code "77") (name "Net-(R$7-2)") (class "Default")
      (node (ref "E$1") (pin "DC§08") (pinfunction "DC§08_DC§08") (pintype "bidirectional"))
      (node (ref "R$7") (pin "OUT") (pinfunction "2_OUT") (pintype "passive"))
    )
    (net (code "78") (name "Net-(R$8-2)") (class "Default")
      (node (ref "E$1") (pin "DC§09") (pinfunction "DC§09_DC§09") (pintype "bidirectional"))
      (node (ref "R$8") (pin "OUT") (pinfunction "2_OUT") (pintype "passive"))
    )
    (net (code "79") (name "Net-(R$9-2)") (class "Default")
      (node (ref "E$1") (pin "DC§10") (pinfunction "DC§10_DC§10") (pintype "bidirectional"))
      (node (ref "R$9") (pin "OUT") (pinfunction "2_OUT") (pintype "passive"))
    )
    (net (code "80") (name "Net-(R$10-2)") (class "Default")
      (node (ref "E$1") (pin "DC§11") (pinfunction "DC§11_DC§11") (pintype "bidirectional"))
      (node (ref "R$10") (pin "OUT") (pinfunction "2_OUT") (pintype "passive"))
    )
    (net (code "81") (name "Net-(R$11-2)") (class "Default")
      (node (ref "E$1") (pin "DC§12") (pinfunction "DC§12_DC§12") (pintype "bidirectional"))
      (node (ref "R$11") (pin "OUT") (pinfunction "2_OUT") (pintype "passive"))
    )
    (net (code "82") (name "Net-(R$12-2)") (class "Default")
      (node (ref "E$1") (pin "DC§13") (pinfunction "DC§13_DC§13") (pintype "bidirectional"))
      (node (ref "R$12") (pin "OUT") (pinfunction "2_OUT") (pintype "passive"))
    )
    (net (code "83") (name "Net-(R$20-2)") (class "Default")
      (node (ref "E$1") (pin "DC§20") (pinfunction "DC§20_DC§20") (pintype "bidirectional"))
      (node (ref "R$20") (pin "OUT") (pinfunction "2_OUT") (pintype "passive"))
    )
    (net (code "84") (name "Net-(R$21-2)") (class "Default")
      (node (ref "E$1") (pin "DC§21") (pinfunction "DC§21_DC§21") (pintype "bidirectional"))
      (node (ref "R$21") (pin "OUT") (pinfunction "2_OUT") (pintype "passive"))
    )
    (net (code "85") (name "Net-(R$22-2)") (class "Default")
      (node (ref "E$1") (pin "DC§22") (pinfunction "DC§22_DC§22") (pintype "bidirectional"))
      (node (ref "R$22") (pin "OUT") (pinfunction "2_OUT") (pintype "passive"))
    )
    (net (code "86") (name "Net-(R$23-2)") (class "Default")
      (node (ref "E$1") (pin "DC§23") (pinfunction "DC§23_DC§23") (pintype "bidirectional"))
      (node (ref "R$23") (pin "OUT") (pinfunction "2_OUT") (pintype "passive"))
    )
    (net (code "87") (name "Net-(R$24-2)") (class "Default")
      (node (ref "E$1") (pin "DC§24") (pinfunction "DC§24_DC§24") (pintype "bidirectional"))
      (node (ref "R$24") (pin "OUT") (pinfunction "2_OUT") (pintype "passive"))
    )
    (net (code "88") (name "Net-(R$25-2)") (class "Default")
      (node (ref "E$1") (pin "DC§07") (pinfunction "DC§07_DC§07") (pintype "bidirectional"))
      (node (ref "R$25") (pin "OUT") (pinfunction "2_OUT") (pintype "passive"))
    )
    (net (code "89") (name "Net-(R$26-2)") (class "Default")
      (node (ref "E$1") (pin "DC§14") (pinfunction "DC§14_DC§14") (pintype "bidirectional"))
      (node (ref "R$26") (pin "OUT") (pinfunction "2_OUT") (pintype "passive"))
    )
    (net (code "90") (name "Net-(R$27-2)") (class "Default")
      (node (ref "E$1") (pin "DC§15") (pinfunction "DC§15_DC§15") (pintype "bidirectional"))
      (node (ref "R$27") (pin "OUT") (pinfunction "2_OUT") (pintype "passive"))
    )
    (net (code "91") (name "Net-(R$28-2)") (class "Default")
      (node (ref "E$1") (pin "DC§16") (pinfunction "DC§16_DC§16") (pintype "bidirectional"))
      (node (ref "R$28") (pin "OUT") (pinfunction "2_OUT") (pintype "passive"))
    )
    (net (code "92") (name "Net-(R$29-2)") (class "Default")
      (node (ref "E$1") (pin "DC§17") (pinfunction "DC§17_DC§17") (pintype "bidirectional"))
      (node (ref "R$29") (pin "OUT") (pinfunction "2_OUT") (pintype "passive"))
    )
    (net (code "93") (name "Net-(R$30-2)") (class "Default")
      (node (ref "E$1") (pin "DC§18") (pinfunction "DC§18_DC§18") (pintype "bidirectional"))
      (node (ref "R$30") (pin "OUT") (pinfunction "2_OUT") (pintype "passive"))
    )
    (net (code "94") (name "Net-(U$3-IN)") (class "Default")
      (node (ref "U$3") (pin "P$1") (pinfunction "IN_P$1") (pintype "bidirectional"))
      (node (ref "U$4") (pin "P$3") (pinfunction "OUT2_P$3") (pintype "bidirectional"))
    )
    (net (code "95") (name "Net-(U$3-OUT1)") (class "Default")
      (node (ref "B$8") (pin "HF") (pinfunction "HF_HF") (pintype "bidirectional"))
      (node (ref "U$3") (pin "P$2") (pinfunction "OUT1_P$2") (pintype "bidirectional"))
    )
    (net (code "96") (name "Net-(U$3-OUT2)") (class "Default")
      (node (ref "B$7") (pin "HF") (pinfunction "HF_HF") (pintype "bidirectional"))
      (node (ref "U$3") (pin "P$3") (pinfunction "OUT2_P$3") (pintype "bidirectional"))
    )
    (net (code "97") (name "Net-(U$4-IN)") (class "Default")
      (node (ref "S$5") (pin "1") (pinfunction "1_1") (pintype "passive"))
      (node (ref "U$4") (pin "P$1") (pinfunction "IN_P$1") (pintype "bidirectional"))
    )
    (net (code "98") (name "Net-(U$4-OUT1)") (class "Default")
      (node (ref "U$4") (pin "P$2") (pinfunction "OUT1_P$2") (pintype "bidirectional"))
      (node (ref "U$5") (pin "P$1") (pinfunction "IN_P$1") (pintype "bidirectional"))
    )
    (net (code "99") (name "Net-(U$5-OUT1)") (class "Default")
      (node (ref "B$10") (pin "HF") (pinfunction "HF_HF") (pintype "bidirectional"))
      (node (ref "U$5") (pin "P$2") (pinfunction "OUT1_P$2") (pintype "bidirectional"))
    )
    (net (code "100") (name "Net-(U$5-OUT2)") (class "Default")
      (node (ref "B$9") (pin "HF") (pinfunction "HF_HF") (pintype "bidirectional"))
      (node (ref "U$5") (pin "P$3") (pinfunction "OUT2_P$3") (pintype "bidirectional"))
    )
    (net (code "101") (name "unconnected-(U$2-PadI$1)") (class "Default")
      (node (ref "U$2") (pin "I$1") (pinfunction "I$1_I$1") (pintype "bidirectional"))
    )
    (net (code "102") (name "unconnected-(U$2-PadI$2)") (class "Default")
      (node (ref "U$2") (pin "I$2") (pinfunction "I$2_I$2") (pintype "bidirectional"))
    )
    (net (code "103") (name "unconnected-(U$2-PadU$1)") (class "Default")
      (node (ref "U$2") (pin "U$1") (pinfunction "U$1_U$1") (pintype "bidirectional"))
    )
    (net (code "104") (name "unconnected-(U$2-PadU$2)") (class "Default")
      (node (ref "U$2") (pin "U$2") (pinfunction "U$2_U$2") (pintype "bidirectional"))
    )
  )
)
